# STM32Sheet.net
KiCad netlist of a schematic drawn in Altium Designer
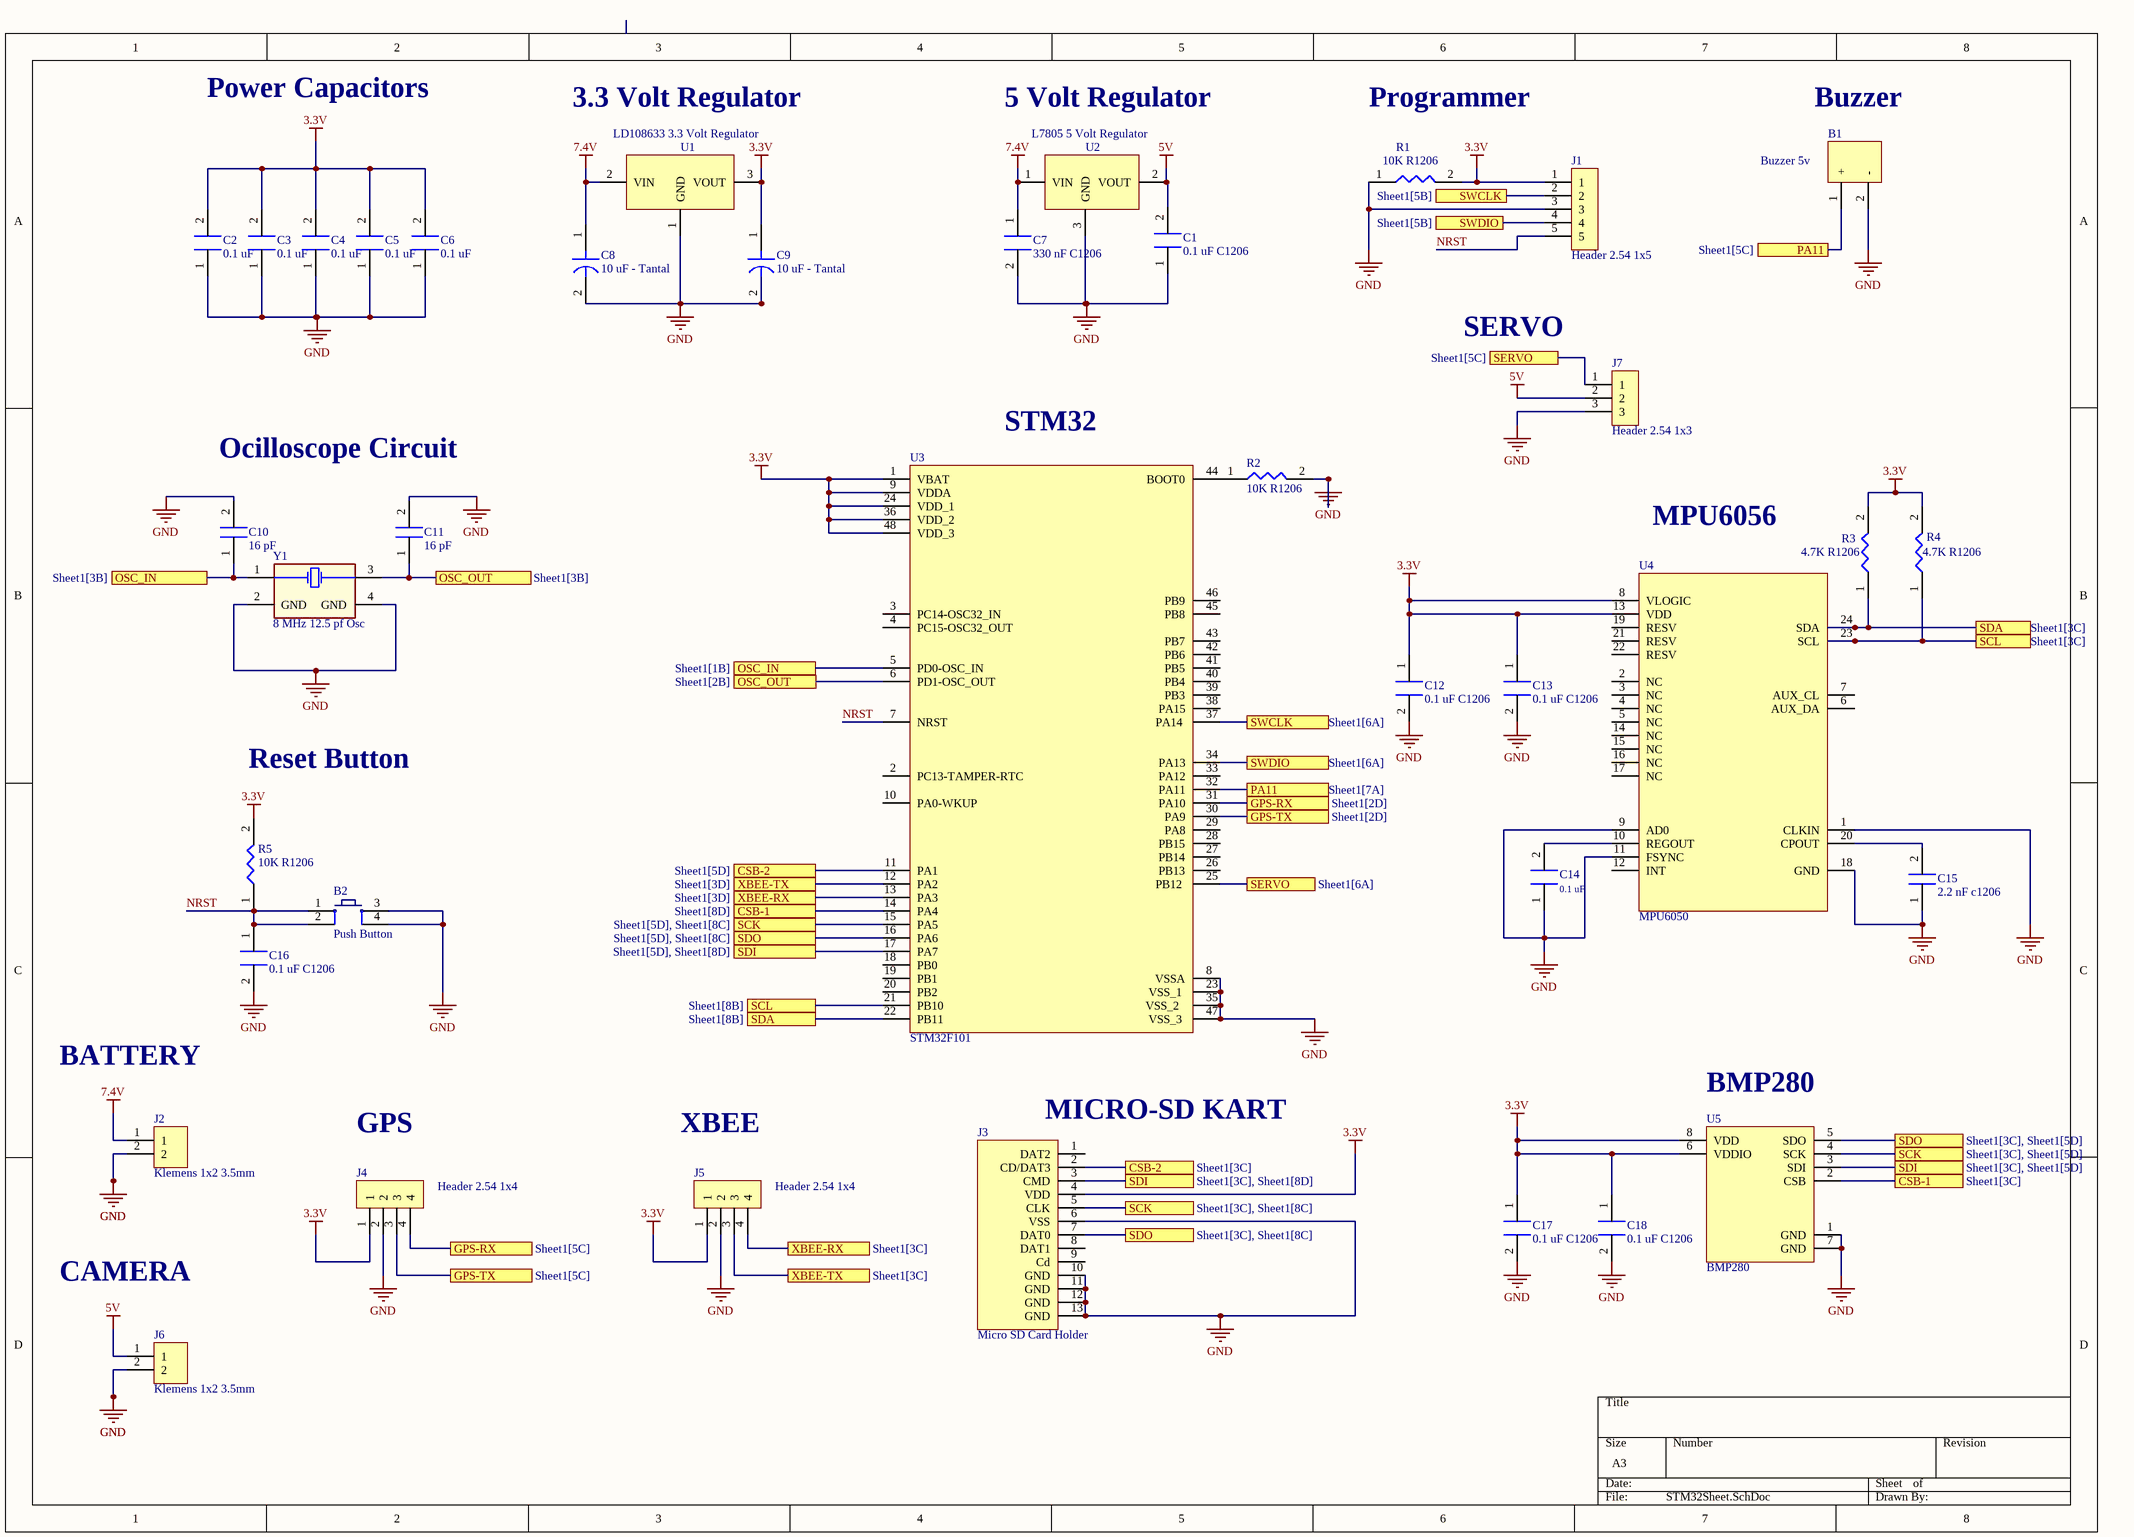
[diagram p0: STM32Sheet.SchDoc]

(export (version "E")
  (design (tool "Eeschema 10.0.6"))
  (components
    (comp (ref "B1") (value "Buzzer 5v") (footprint "Buzzer 5v") (libsource (lib "STM32") (part "Buzzer 5v")))
    (comp (ref "B2")
      (value "Push Button")
      (footprint "PUSB BUTTON-SMD")
      (description "Smd Push Button")
      (libsource (lib "STM32") (part "Push Button"))
    )
    (comp (ref "C1")
      (value "0.1 uF C1206")
      (footprint "C1206")
      (libsource (lib "STM32") (part "0.1 uF C1206"))
    )
    (comp (ref "C2")
      (value "0.1 uF")
      (footprint "C1206")
      (description "0.1 uF C1206")
      (libsource (lib "STM32") (part "0.1 uF C1206"))
    )
    (comp (ref "C3")
      (value "0.1 uF")
      (footprint "C1206")
      (description "0.1 uF C1206")
      (libsource (lib "STM32") (part "0.1 uF C1206"))
    )
    (comp (ref "C4")
      (value "0.1 uF")
      (footprint "C1206")
      (description "0.1 uF C1206")
      (libsource (lib "STM32") (part "0.1 uF C1206"))
    )
    (comp (ref "C5")
      (value "0.1 uF")
      (footprint "C1206")
      (description "0.1 uF C1206")
      (libsource (lib "STM32") (part "0.1 uF C1206"))
    )
    (comp (ref "C6")
      (value "0.1 uF")
      (footprint "C1206")
      (description "0.1 uF C1206")
      (libsource (lib "STM32") (part "0.1 uF C1206"))
    )
    (comp (ref "C7")
      (value "330 nF C1206")
      (footprint "C1206")
      (libsource (lib "STM32") (part "330 nF C1206"))
    )
    (comp (ref "C8")
      (value "10 uF - Tantal")
      (footprint "C1206- TANTAL")
      (libsource (lib "STM32") (part "10 uF - Tantal"))
    )
    (comp (ref "C9")
      (value "10 uF - Tantal")
      (footprint "C1206- TANTAL")
      (libsource (lib "STM32") (part "10 uF - Tantal"))
    )
    (comp (ref "C10") (value "16 pF") (footprint "C1206") (libsource (lib "STM32") (part "16 pF")))
    (comp (ref "C11") (value "16 pF") (footprint "C1206") (libsource (lib "STM32") (part "16 pF")))
    (comp (ref "C12")
      (value "0.1 uF C1206")
      (footprint "C1206")
      (libsource (lib "STM32") (part "0.1 uF C1206"))
    )
    (comp (ref "C13")
      (value "0.1 uF C1206")
      (footprint "C1206")
      (libsource (lib "STM32") (part "0.1 uF C1206"))
    )
    (comp (ref "C14")
      (value "0.1 uF")
      (footprint "C1206")
      (description "0.1 uF C1206")
      (libsource (lib "STM32") (part "0.1 uF C1206"))
    )
    (comp (ref "C15")
      (value "2.2 nF c1206")
      (footprint "C1206")
      (libsource (lib "STM32") (part "2.2 nF c1206"))
    )
    (comp (ref "C16")
      (value "0.1 uF C1206")
      (footprint "C1206")
      (libsource (lib "STM32") (part "0.1 uF C1206"))
    )
    (comp (ref "C17")
      (value "0.1 uF C1206")
      (footprint "C1206")
      (libsource (lib "STM32") (part "0.1 uF C1206"))
    )
    (comp (ref "C18")
      (value "0.1 uF C1206")
      (footprint "C1206")
      (libsource (lib "STM32") (part "0.1 uF C1206"))
    )
    (comp (ref "J1")
      (value "Header 2.54 1x5")
      (footprint "Header 2.54 1x5")
      (libsource (lib "STM32") (part "Header 2.54 1x5"))
    )
    (comp (ref "J2")
      (value "Klemens 1x2 3.5mm")
      (footprint "Klemens 1x2 - 3.5mm")
      (libsource (lib "STM32") (part "Klemens 1x2 3.5mm"))
    )
    (comp (ref "J3")
      (value "Micro SD Card Holder")
      (footprint "Micro SD Card Holder")
      (libsource (lib "STM32") (part "Micro SD Card Holder"))
    )
    (comp (ref "J4")
      (value "Header 2.54 1x4")
      (footprint "Header 2.54 1x4")
      (libsource (lib "STM32") (part "Header 2.54 1x4"))
    )
    (comp (ref "J5")
      (value "Header 2.54 1x4")
      (footprint "Header 2.54 1x4")
      (libsource (lib "STM32") (part "Header 2.54 1x4"))
    )
    (comp (ref "J6")
      (value "Klemens 1x2 3.5mm")
      (footprint "Klemens 1x2 - 3.5mm")
      (libsource (lib "STM32") (part "Klemens 1x2 3.5mm"))
    )
    (comp (ref "J7")
      (value "Header 2.54 1x3")
      (footprint "Header 2.54 1x3")
      (libsource (lib "STM32") (part "Header 2.54 1x3"))
    )
    (comp (ref "R1")
      (value "10K R1206")
      (footprint "R1206 Resistor")
      (libsource (lib "STM32") (part "10K R1206"))
    )
    (comp (ref "R2")
      (value "10K R1206")
      (footprint "R1206 Resistor")
      (libsource (lib "STM32") (part "10K R1206"))
    )
    (comp (ref "R3")
      (value "4.7K R1206")
      (footprint "R1206 Resistor")
      (libsource (lib "STM32") (part "4.7K R1206"))
    )
    (comp (ref "R4")
      (value "4.7K R1206")
      (footprint "R1206 Resistor")
      (libsource (lib "STM32") (part "4.7K R1206"))
    )
    (comp (ref "R5")
      (value "10K R1206")
      (footprint "R1206 Resistor")
      (libsource (lib "STM32") (part "10K R1206"))
    )
    (comp (ref "U1")
      (value "LD108633 3.3 Volt Regulator")
      (footprint "DPAK228P972X230-3N")
      (description "LD1086 3.3V REGULATOR")
      (libsource (lib "STM32") (part "LD108633 DPAK"))
    )
    (comp (ref "U2")
      (value "L7805 5 Volt Regulator")
      (footprint "DPAK228P972X230-3N")
      (description "L7805 5V REGULATOR. SMD PAKET")
      (libsource (lib "STM32") (part "L7805-DPAK"))
    )
    (comp (ref "U3")
      (value "STM32F101")
      (footprint "LQFP48-STM")
      (description "STM32F101 48 PİNLİ MİKROİŞLEMCİ")
      (libsource (lib "STM32") (part "STM32F101"))
    )
    (comp (ref "U4")
      (value "MPU6050")
      (footprint "QFN50P400X400X90_HS-25N")
      (description "MPU6050 GYRO")
      (libsource (lib "STM32") (part "MPU6050"))
    )
    (comp (ref "U5")
      (value "BMP280")
      (footprint "BMP280")
      (description "BMP280 SENSOR")
      (libsource (lib "STM32") (part "BMP280"))
    )
    (comp (ref "Y1")
      (value "8 MHz 12.5 pf Osc")
      (footprint "8 MHZ Osc.")
      (libsource (lib "STM32") (part "8 MHz 12.5 pf Osc"))
    )
  )
  (nets
    (net (code "1") (name "/CSB-1") (class "Default")
      (node (ref "U3") (pin "14") (pinfunction "PA4_14") (pintype "passive"))
      (node (ref "U5") (pin "2") (pinfunction "CSB_2") (pintype "passive"))
    )
    (net (code "2") (name "/CSB-2") (class "Default")
      (node (ref "J3") (pin "2") (pinfunction "CD/DAT3_2") (pintype "passive"))
      (node (ref "U3") (pin "11") (pinfunction "PA1_11") (pintype "passive"))
    )
    (net (code "3") (name "/GPS-RX") (class "Default")
      (node (ref "J4") (pin "4") (pinfunction "4_4") (pintype "passive"))
      (node (ref "U3") (pin "31") (pinfunction "PA10_31") (pintype "passive"))
    )
    (net (code "4") (name "/GPS-TX") (class "Default")
      (node (ref "J4") (pin "3") (pinfunction "3_3") (pintype "passive"))
      (node (ref "U3") (pin "30") (pinfunction "PA9_30") (pintype "passive"))
    )
    (net (code "5") (name "/NRST") (class "Default")
      (node (ref "B2") (pin "1") (pinfunction "1_1") (pintype "passive"))
      (node (ref "B2") (pin "2") (pinfunction "2_2") (pintype "passive"))
      (node (ref "C16") (pin "1") (pinfunction "1_1") (pintype "passive"))
      (node (ref "J1") (pin "5") (pinfunction "5_5") (pintype "passive"))
      (node (ref "R5") (pin "1") (pinfunction "1_1") (pintype "passive"))
      (node (ref "U3") (pin "7") (pinfunction "NRST_7") (pintype "passive"))
    )
    (net (code "6") (name "/OSC_IN") (class "Default")
      (node (ref "C10") (pin "1") (pinfunction "1_1") (pintype "passive"))
      (node (ref "U3") (pin "5") (pinfunction "PD0-OSC_IN_5") (pintype "passive"))
      (node (ref "Y1") (pin "1") (pintype "power_in"))
    )
    (net (code "7") (name "/OSC_OUT") (class "Default")
      (node (ref "C11") (pin "1") (pinfunction "1_1") (pintype "passive"))
      (node (ref "U3") (pin "6") (pinfunction "PD1-OSC_OUT_6") (pintype "passive"))
      (node (ref "Y1") (pin "3") (pintype "passive"))
    )
    (net (code "8") (name "/PA11") (class "Default")
      (node (ref "B1") (pin "1") (pinfunction "+_1") (pintype "passive"))
      (node (ref "U3") (pin "32") (pinfunction "PA11_32") (pintype "passive"))
    )
    (net (code "9") (name "/SCK") (class "Default")
      (node (ref "J3") (pin "5") (pinfunction "CLK_5") (pintype "passive"))
      (node (ref "U3") (pin "15") (pinfunction "PA5_15") (pintype "passive"))
      (node (ref "U5") (pin "4") (pinfunction "SCK_4") (pintype "passive"))
    )
    (net (code "10") (name "/SCL") (class "Default")
      (node (ref "R4") (pin "1") (pinfunction "1_1") (pintype "passive"))
      (node (ref "U3") (pin "21") (pinfunction "PB10_21") (pintype "passive"))
      (node (ref "U4") (pin "23") (pinfunction "SCL_23") (pintype "passive"))
    )
    (net (code "11") (name "/SDA") (class "Default")
      (node (ref "R3") (pin "1") (pinfunction "1_1") (pintype "passive"))
      (node (ref "U3") (pin "22") (pinfunction "PB11_22") (pintype "passive"))
      (node (ref "U4") (pin "24") (pinfunction "SDA_24") (pintype "passive"))
    )
    (net (code "12") (name "/SDI") (class "Default")
      (node (ref "J3") (pin "3") (pinfunction "CMD_3") (pintype "passive"))
      (node (ref "U3") (pin "17") (pinfunction "PA7_17") (pintype "passive"))
      (node (ref "U5") (pin "3") (pinfunction "SDI_3") (pintype "passive"))
    )
    (net (code "13") (name "/SDO") (class "Default")
      (node (ref "J3") (pin "7") (pinfunction "DAT0_7") (pintype "passive"))
      (node (ref "U3") (pin "16") (pinfunction "PA6_16") (pintype "passive"))
      (node (ref "U5") (pin "5") (pinfunction "SDO_5") (pintype "passive"))
    )
    (net (code "14") (name "/SERVO") (class "Default")
      (node (ref "J7") (pin "1") (pinfunction "1_1") (pintype "passive"))
      (node (ref "U3") (pin "25") (pinfunction "PB12_25") (pintype "passive"))
    )
    (net (code "15") (name "/SWCLK") (class "Default")
      (node (ref "J1") (pin "2") (pinfunction "2_2") (pintype "passive"))
      (node (ref "U3") (pin "37") (pinfunction "PA14_37") (pintype "passive"))
    )
    (net (code "16") (name "/SWDIO") (class "Default")
      (node (ref "J1") (pin "4") (pinfunction "4_4") (pintype "passive"))
      (node (ref "U3") (pin "34") (pinfunction "PA13_34") (pintype "passive"))
    )
    (net (code "17") (name "/XBEE-RX") (class "Default")
      (node (ref "J5") (pin "4") (pinfunction "4_4") (pintype "passive"))
      (node (ref "U3") (pin "13") (pinfunction "PA3_13") (pintype "passive"))
    )
    (net (code "18") (name "/XBEE-TX") (class "Default")
      (node (ref "J5") (pin "3") (pinfunction "3_3") (pintype "passive"))
      (node (ref "U3") (pin "12") (pinfunction "PA2_12") (pintype "passive"))
    )
    (net (code "19") (name "3.3V") (class "Default")
      (node (ref "C12") (pin "1") (pinfunction "1_1") (pintype "passive"))
      (node (ref "C13") (pin "1") (pinfunction "1_1") (pintype "passive"))
      (node (ref "C17") (pin "1") (pinfunction "1_1") (pintype "passive"))
      (node (ref "C18") (pin "1") (pinfunction "1_1") (pintype "passive"))
      (node (ref "C2") (pin "2") (pinfunction "2_2") (pintype "passive"))
      (node (ref "C3") (pin "2") (pinfunction "2_2") (pintype "passive"))
      (node (ref "C4") (pin "2") (pinfunction "2_2") (pintype "passive"))
      (node (ref "C5") (pin "2") (pinfunction "2_2") (pintype "passive"))
      (node (ref "C6") (pin "2") (pinfunction "2_2") (pintype "passive"))
      (node (ref "C9") (pin "1") (pinfunction "1_1") (pintype "passive"))
      (node (ref "J1") (pin "1") (pinfunction "1_1") (pintype "passive"))
      (node (ref "J3") (pin "4") (pinfunction "VDD_4") (pintype "passive"))
      (node (ref "J4") (pin "1") (pinfunction "1_1") (pintype "passive"))
      (node (ref "J5") (pin "1") (pinfunction "1_1") (pintype "passive"))
      (node (ref "R1") (pin "2") (pinfunction "2_2") (pintype "passive"))
      (node (ref "R3") (pin "2") (pinfunction "2_2") (pintype "passive"))
      (node (ref "R4") (pin "2") (pinfunction "2_2") (pintype "passive"))
      (node (ref "R5") (pin "2") (pinfunction "2_2") (pintype "passive"))
      (node (ref "U1") (pin "3") (pinfunction "VOUT_3") (pintype "passive"))
      (node (ref "U3") (pin "1") (pinfunction "VBAT_1") (pintype "passive"))
      (node (ref "U3") (pin "24") (pinfunction "VDD_1_24") (pintype "passive"))
      (node (ref "U3") (pin "36") (pinfunction "VDD_2_36") (pintype "passive"))
      (node (ref "U3") (pin "48") (pinfunction "VDD_3_48") (pintype "passive"))
      (node (ref "U3") (pin "9") (pinfunction "VDDA_9") (pintype "passive"))
      (node (ref "U4") (pin "13") (pinfunction "VDD_13") (pintype "passive"))
      (node (ref "U4") (pin "8") (pinfunction "VLOGIC_8") (pintype "passive"))
      (node (ref "U5") (pin "6") (pinfunction "VDDIO_6") (pintype "passive"))
      (node (ref "U5") (pin "8") (pinfunction "VDD_8") (pintype "passive"))
    )
    (net (code "20") (name "5V") (class "Default")
      (node (ref "C1") (pin "2") (pinfunction "2_2") (pintype "passive"))
      (node (ref "J6") (pin "1") (pinfunction "1_1") (pintype "passive"))
      (node (ref "J7") (pin "2") (pinfunction "2_2") (pintype "passive"))
      (node (ref "U2") (pin "2") (pinfunction "VOUT_2") (pintype "passive"))
    )
    (net (code "21") (name "7.4V") (class "Default")
      (node (ref "C7") (pin "1") (pinfunction "1_1") (pintype "passive"))
      (node (ref "C8") (pin "1") (pinfunction "1_1") (pintype "passive"))
      (node (ref "J2") (pin "1") (pinfunction "1_1") (pintype "passive"))
      (node (ref "U1") (pin "2") (pinfunction "VIN_2") (pintype "passive"))
      (node (ref "U2") (pin "1") (pinfunction "VIN_1") (pintype "passive"))
    )
    (net (code "22") (name "GND") (class "Default")
      (node (ref "B1") (pin "2") (pinfunction "-_2") (pintype "passive"))
      (node (ref "B2") (pin "3") (pinfunction "3_3") (pintype "passive"))
      (node (ref "B2") (pin "4") (pinfunction "4_4") (pintype "passive"))
      (node (ref "C1") (pin "1") (pinfunction "1_1") (pintype "passive"))
      (node (ref "C10") (pin "2") (pinfunction "2_2") (pintype "passive"))
      (node (ref "C11") (pin "2") (pinfunction "2_2") (pintype "passive"))
      (node (ref "C12") (pin "2") (pinfunction "2_2") (pintype "passive"))
      (node (ref "C13") (pin "2") (pinfunction "2_2") (pintype "passive"))
      (node (ref "C14") (pin "1") (pinfunction "1_1") (pintype "passive"))
      (node (ref "C15") (pin "1") (pinfunction "1_1") (pintype "passive"))
      (node (ref "C16") (pin "2") (pinfunction "2_2") (pintype "passive"))
      (node (ref "C17") (pin "2") (pinfunction "2_2") (pintype "passive"))
      (node (ref "C18") (pin "2") (pinfunction "2_2") (pintype "passive"))
      (node (ref "C2") (pin "1") (pinfunction "1_1") (pintype "passive"))
      (node (ref "C3") (pin "1") (pinfunction "1_1") (pintype "passive"))
      (node (ref "C4") (pin "1") (pinfunction "1_1") (pintype "passive"))
      (node (ref "C5") (pin "1") (pinfunction "1_1") (pintype "passive"))
      (node (ref "C6") (pin "1") (pinfunction "1_1") (pintype "passive"))
      (node (ref "C7") (pin "2") (pinfunction "2_2") (pintype "passive"))
      (node (ref "C8") (pin "2") (pinfunction "2_2") (pintype "passive"))
      (node (ref "C9") (pin "2") (pinfunction "2_2") (pintype "passive"))
      (node (ref "J1") (pin "3") (pinfunction "3_3") (pintype "passive"))
      (node (ref "J2") (pin "2") (pinfunction "2_2") (pintype "passive"))
      (node (ref "J3") (pin "10") (pinfunction "GND_10") (pintype "passive"))
      (node (ref "J3") (pin "11") (pinfunction "GND_11") (pintype "passive"))
      (node (ref "J3") (pin "12") (pinfunction "GND_12") (pintype "passive"))
      (node (ref "J3") (pin "13") (pinfunction "GND_13") (pintype "passive"))
      (node (ref "J3") (pin "6") (pinfunction "VSS_6") (pintype "passive"))
      (node (ref "J4") (pin "2") (pinfunction "2_2") (pintype "passive"))
      (node (ref "J5") (pin "2") (pinfunction "2_2") (pintype "passive"))
      (node (ref "J6") (pin "2") (pinfunction "2_2") (pintype "passive"))
      (node (ref "J7") (pin "3") (pinfunction "3_3") (pintype "passive"))
      (node (ref "R1") (pin "1") (pinfunction "1_1") (pintype "passive"))
      (node (ref "R2") (pin "2") (pinfunction "2_2") (pintype "passive"))
      (node (ref "U1") (pin "1") (pinfunction "GND_1") (pintype "passive"))
      (node (ref "U2") (pin "3") (pinfunction "GND_3") (pintype "passive"))
      (node (ref "U3") (pin "23") (pinfunction "VSS_1_23") (pintype "passive"))
      (node (ref "U3") (pin "35") (pinfunction "VSS_2_35") (pintype "passive"))
      (node (ref "U3") (pin "47") (pinfunction "VSS_3_47") (pintype "passive"))
      (node (ref "U3") (pin "8") (pinfunction "VSSA_8") (pintype "passive"))
      (node (ref "U4") (pin "1") (pinfunction "CLKIN_1") (pintype "passive"))
      (node (ref "U4") (pin "11") (pinfunction "FSYNC_11") (pintype "passive"))
      (node (ref "U4") (pin "18") (pinfunction "GND_18") (pintype "passive"))
      (node (ref "U4") (pin "9") (pinfunction "AD0_9") (pintype "passive"))
      (node (ref "U5") (pin "1") (pinfunction "GND_1") (pintype "passive"))
      (node (ref "U5") (pin "7") (pinfunction "GND_7") (pintype "passive"))
      (node (ref "Y1") (pin "2") (pinfunction "GND_2") (pintype "power_in"))
      (node (ref "Y1") (pin "4") (pinfunction "GND_4") (pintype "passive"))
    )
    (net (code "23") (name "Net-(U3-BOOT0)") (class "Default")
      (node (ref "R2") (pin "1") (pinfunction "1_1") (pintype "passive"))
      (node (ref "U3") (pin "44") (pinfunction "BOOT0_44") (pintype "passive"))
    )
    (net (code "24") (name "Net-(U4-CPOUT)") (class "Default")
      (node (ref "C15") (pin "2") (pinfunction "2_2") (pintype "passive"))
      (node (ref "U4") (pin "20") (pinfunction "CPOUT_20") (pintype "passive"))
    )
    (net (code "25") (name "Net-(U4-REGOUT)") (class "Default")
      (node (ref "C14") (pin "2") (pinfunction "2_2") (pintype "passive"))
      (node (ref "U4") (pin "10") (pinfunction "REGOUT_10") (pintype "passive"))
    )
    (net (code "26") (name "unconnected-(J3-Cd-Pad9)") (class "Default")
      (node (ref "J3") (pin "9") (pinfunction "Cd_9") (pintype "passive"))
    )
    (net (code "27") (name "unconnected-(J3-DAT1-Pad8)") (class "Default")
      (node (ref "J3") (pin "8") (pinfunction "DAT1_8") (pintype "passive"))
    )
    (net (code "28") (name "unconnected-(J3-DAT2-Pad1)") (class "Default")
      (node (ref "J3") (pin "1") (pinfunction "DAT2_1") (pintype "passive"))
    )
    (net (code "29") (name "unconnected-(U3-PA0-WKUP-Pad10)") (class "Default")
      (node (ref "U3") (pin "10") (pinfunction "PA0-WKUP_10") (pintype "passive"))
    )
    (net (code "30") (name "unconnected-(U3-PA8-Pad29)") (class "Default")
      (node (ref "U3") (pin "29") (pinfunction "PA8_29") (pintype "passive"))
    )
    (net (code "31") (name "unconnected-(U3-PA12-Pad33)") (class "Default")
      (node (ref "U3") (pin "33") (pinfunction "PA12_33") (pintype "passive"))
    )
    (net (code "32") (name "unconnected-(U3-PA15-Pad38)") (class "Default")
      (node (ref "U3") (pin "38") (pinfunction "PA15_38") (pintype "passive"))
    )
    (net (code "33") (name "unconnected-(U3-PB0-Pad18)") (class "Default")
      (node (ref "U3") (pin "18") (pinfunction "PB0_18") (pintype "passive"))
    )
    (net (code "34") (name "unconnected-(U3-PB1-Pad19)") (class "Default")
      (node (ref "U3") (pin "19") (pinfunction "PB1_19") (pintype "passive"))
    )
    (net (code "35") (name "unconnected-(U3-PB2-Pad20)") (class "Default")
      (node (ref "U3") (pin "20") (pinfunction "PB2_20") (pintype "passive"))
    )
    (net (code "36") (name "unconnected-(U3-PB3-Pad39)") (class "Default")
      (node (ref "U3") (pin "39") (pinfunction "PB3_39") (pintype "passive"))
    )
    (net (code "37") (name "unconnected-(U3-PB4-Pad40)") (class "Default")
      (node (ref "U3") (pin "40") (pinfunction "PB4_40") (pintype "passive"))
    )
    (net (code "38") (name "unconnected-(U3-PB5-Pad41)") (class "Default")
      (node (ref "U3") (pin "41") (pinfunction "PB5_41") (pintype "passive"))
    )
    (net (code "39") (name "unconnected-(U3-PB6-Pad42)") (class "Default")
      (node (ref "U3") (pin "42") (pinfunction "PB6_42") (pintype "passive"))
    )
    (net (code "40") (name "unconnected-(U3-PB7-Pad43)") (class "Default")
      (node (ref "U3") (pin "43") (pinfunction "PB7_43") (pintype "passive"))
    )
    (net (code "41") (name "unconnected-(U3-PB8-Pad45)") (class "Default")
      (node (ref "U3") (pin "45") (pinfunction "PB8_45") (pintype "passive"))
    )
    (net (code "42") (name "unconnected-(U3-PB9-Pad46)") (class "Default")
      (node (ref "U3") (pin "46") (pinfunction "PB9_46") (pintype "passive"))
    )
    (net (code "43") (name "unconnected-(U3-PB13-Pad26)") (class "Default")
      (node (ref "U3") (pin "26") (pinfunction "PB13_26") (pintype "passive"))
    )
    (net (code "44") (name "unconnected-(U3-PB14-Pad27)") (class "Default")
      (node (ref "U3") (pin "27") (pinfunction "PB14_27") (pintype "passive"))
    )
    (net (code "45") (name "unconnected-(U3-PB15-Pad28)") (class "Default")
      (node (ref "U3") (pin "28") (pinfunction "PB15_28") (pintype "passive"))
    )
    (net (code "46") (name "unconnected-(U3-PC13-TAMPER-RTC-Pad2)") (class "Default")
      (node (ref "U3") (pin "2") (pinfunction "PC13-TAMPER-RTC_2") (pintype "passive"))
    )
    (net (code "47") (name "unconnected-(U3-PC14-OSC32_IN-Pad3)") (class "Default")
      (node (ref "U3") (pin "3") (pinfunction "PC14-OSC32_IN_3") (pintype "passive"))
    )
    (net (code "48") (name "unconnected-(U3-PC15-OSC32_OUT-Pad4)") (class "Default")
      (node (ref "U3") (pin "4") (pinfunction "PC15-OSC32_OUT_4") (pintype "passive"))
    )
    (net (code "49") (name "unconnected-(U4-AUX_CL-Pad7)") (class "Default")
      (node (ref "U4") (pin "7") (pinfunction "AUX_CL_7") (pintype "passive"))
    )
    (net (code "50") (name "unconnected-(U4-AUX_DA-Pad6)") (class "Default")
      (node (ref "U4") (pin "6") (pinfunction "AUX_DA_6") (pintype "passive"))
    )
    (net (code "51") (name "unconnected-(U4-INT-Pad12)") (class "Default")
      (node (ref "U4") (pin "12") (pinfunction "INT_12") (pintype "passive"))
    )
    (net (code "52") (name "unconnected-(U4-NC-Pad2)") (class "Default")
      (node (ref "U4") (pin "2") (pinfunction "NC_2") (pintype "passive"))
    )
    (net (code "53") (name "unconnected-(U4-NC-Pad3)") (class "Default")
      (node (ref "U4") (pin "3") (pinfunction "NC_3") (pintype "passive"))
    )
    (net (code "54") (name "unconnected-(U4-NC-Pad4)") (class "Default")
      (node (ref "U4") (pin "4") (pinfunction "NC_4") (pintype "passive"))
    )
    (net (code "55") (name "unconnected-(U4-NC-Pad5)") (class "Default")
      (node (ref "U4") (pin "5") (pinfunction "NC_5") (pintype "passive"))
    )
    (net (code "56") (name "unconnected-(U4-NC-Pad14)") (class "Default")
      (node (ref "U4") (pin "14") (pinfunction "NC_14") (pintype "passive"))
    )
    (net (code "57") (name "unconnected-(U4-NC-Pad15)") (class "Default")
      (node (ref "U4") (pin "15") (pinfunction "NC_15") (pintype "passive"))
    )
    (net (code "58") (name "unconnected-(U4-NC-Pad16)") (class "Default")
      (node (ref "U4") (pin "16") (pinfunction "NC_16") (pintype "passive"))
    )
    (net (code "59") (name "unconnected-(U4-NC-Pad17)") (class "Default")
      (node (ref "U4") (pin "17") (pinfunction "NC_17") (pintype "passive"))
    )
    (net (code "60") (name "unconnected-(U4-RESV-Pad19)") (class "Default")
      (node (ref "U4") (pin "19") (pinfunction "RESV_19") (pintype "passive"))
    )
    (net (code "61") (name "unconnected-(U4-RESV-Pad21)") (class "Default")
      (node (ref "U4") (pin "21") (pinfunction "RESV_21") (pintype "passive"))
    )
    (net (code "62") (name "unconnected-(U4-RESV-Pad22)") (class "Default")
      (node (ref "U4") (pin "22") (pinfunction "RESV_22") (pintype "passive"))
    )
  )
)
